# display_in4.net
KiCad netlist of a schematic drawn in EAGLE
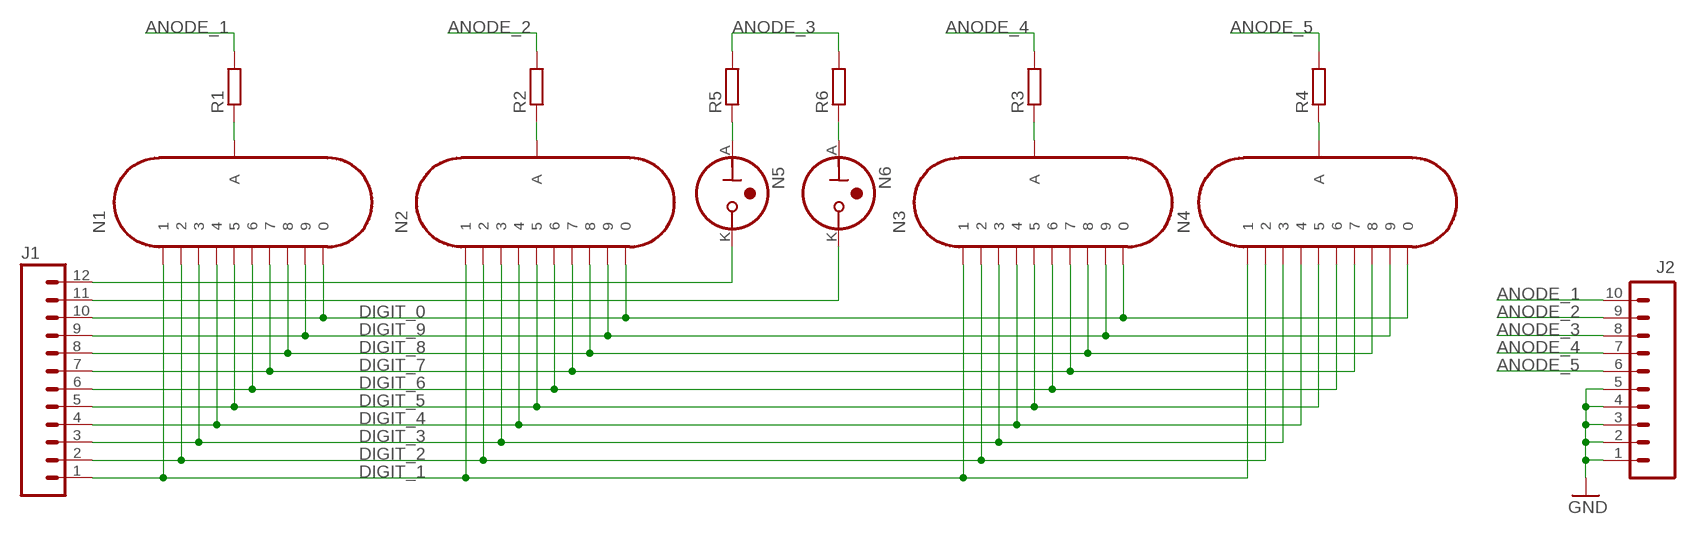
[diagram p0: schematic, sheet 1]

(export (version "E")
  (design (tool "Eeschema 10.0.6"))
  (components
    (comp (ref "J1")
      (value "M12LOCK")
      (footprint "eagle-import:1X12_LOCK")
      (libsource (lib "eagle-import") (part "M12LOCK"))
    )
    (comp (ref "J2")
      (value "M10LOCK")
      (footprint "eagle-import:1X10_LOCK")
      (libsource (lib "eagle-import") (part "M10LOCK"))
    )
    (comp (ref "N1")
      (value "IN-4")
      (footprint "eagle-import:IN-4")
      (libsource (lib "eagle-import") (part "IN-4"))
    )
    (comp (ref "N2")
      (value "IN-4")
      (footprint "eagle-import:IN-4")
      (libsource (lib "eagle-import") (part "IN-4"))
    )
    (comp (ref "N3")
      (value "IN-4")
      (footprint "eagle-import:IN-4")
      (libsource (lib "eagle-import") (part "IN-4"))
    )
    (comp (ref "N4")
      (value "IN-4")
      (footprint "eagle-import:IN-4")
      (libsource (lib "eagle-import") (part "IN-4"))
    )
    (comp (ref "N5")
      (value "IN-6")
      (footprint "eagle-import:IN-6")
      (libsource (lib "eagle-import") (part "IN-6"))
    )
    (comp (ref "N6")
      (value "IN-6")
      (footprint "eagle-import:IN-6")
      (libsource (lib "eagle-import") (part "IN-6"))
    )
    (comp (ref "R1")
      (value "R-EU_0204/7")
      (footprint "eagle-import:0204_7")
      (libsource (lib "eagle-import") (part "R-EU_0204/7"))
    )
    (comp (ref "R2")
      (value "R-EU_0204/7")
      (footprint "eagle-import:0204_7")
      (libsource (lib "eagle-import") (part "R-EU_0204/7"))
    )
    (comp (ref "R3")
      (value "R-EU_0204/7")
      (footprint "eagle-import:0204_7")
      (libsource (lib "eagle-import") (part "R-EU_0204/7"))
    )
    (comp (ref "R4")
      (value "R-EU_0204/7")
      (footprint "eagle-import:0204_7")
      (libsource (lib "eagle-import") (part "R-EU_0204/7"))
    )
    (comp (ref "R5")
      (value "R-EU_0204/7")
      (footprint "eagle-import:0204_7")
      (libsource (lib "eagle-import") (part "R-EU_0204/7"))
    )
    (comp (ref "R6")
      (value "R-EU_0204/7")
      (footprint "eagle-import:0204_7")
      (libsource (lib "eagle-import") (part "R-EU_0204/7"))
    )
  )
  (nets
    (net (code "1") (name "/ANODE_1") (class "Default")
      (node (ref "J2") (pin "10") (pinfunction "10_10") (pintype "passive"))
      (node (ref "R1") (pin "2") (pinfunction "2_2") (pintype "passive"))
    )
    (net (code "2") (name "/ANODE_2") (class "Default")
      (node (ref "J2") (pin "9") (pinfunction "9_9") (pintype "passive"))
      (node (ref "R2") (pin "2") (pinfunction "2_2") (pintype "passive"))
    )
    (net (code "3") (name "/ANODE_3") (class "Default")
      (node (ref "J2") (pin "8") (pinfunction "8_8") (pintype "passive"))
      (node (ref "R5") (pin "2") (pinfunction "2_2") (pintype "passive"))
      (node (ref "R6") (pin "2") (pinfunction "2_2") (pintype "passive"))
    )
    (net (code "4") (name "/ANODE_4") (class "Default")
      (node (ref "J2") (pin "7") (pinfunction "7_7") (pintype "passive"))
      (node (ref "R3") (pin "2") (pinfunction "2_2") (pintype "passive"))
    )
    (net (code "5") (name "/ANODE_5") (class "Default")
      (node (ref "J2") (pin "6") (pinfunction "6_6") (pintype "passive"))
      (node (ref "R4") (pin "2") (pinfunction "2_2") (pintype "passive"))
    )
    (net (code "6") (name "/DIGIT_0") (class "Default")
      (node (ref "J1") (pin "10") (pinfunction "10_10") (pintype "passive"))
      (node (ref "N1") (pin "8") (pinfunction "0_8") (pintype "bidirectional"))
      (node (ref "N2") (pin "8") (pinfunction "0_8") (pintype "bidirectional"))
      (node (ref "N3") (pin "8") (pinfunction "0_8") (pintype "bidirectional"))
      (node (ref "N4") (pin "8") (pinfunction "0_8") (pintype "bidirectional"))
    )
    (net (code "7") (name "/DIGIT_1") (class "Default")
      (node (ref "J1") (pin "1") (pinfunction "1_1") (pintype "passive"))
      (node (ref "N1") (pin "14") (pinfunction "1_14") (pintype "bidirectional"))
      (node (ref "N2") (pin "14") (pinfunction "1_14") (pintype "bidirectional"))
      (node (ref "N3") (pin "14") (pinfunction "1_14") (pintype "bidirectional"))
      (node (ref "N4") (pin "14") (pinfunction "1_14") (pintype "bidirectional"))
    )
    (net (code "8") (name "/DIGIT_2") (class "Default")
      (node (ref "J1") (pin "2") (pinfunction "2_2") (pintype "passive"))
      (node (ref "N1") (pin "9") (pinfunction "2_9") (pintype "bidirectional"))
      (node (ref "N2") (pin "9") (pinfunction "2_9") (pintype "bidirectional"))
      (node (ref "N3") (pin "9") (pinfunction "2_9") (pintype "bidirectional"))
      (node (ref "N4") (pin "9") (pinfunction "2_9") (pintype "bidirectional"))
    )
    (net (code "9") (name "/DIGIT_3") (class "Default")
      (node (ref "J1") (pin "3") (pinfunction "3_3") (pintype "passive"))
      (node (ref "N1") (pin "11") (pinfunction "3_11") (pintype "bidirectional"))
      (node (ref "N2") (pin "11") (pinfunction "3_11") (pintype "bidirectional"))
      (node (ref "N3") (pin "11") (pinfunction "3_11") (pintype "bidirectional"))
      (node (ref "N4") (pin "11") (pinfunction "3_11") (pintype "bidirectional"))
    )
    (net (code "10") (name "/DIGIT_4") (class "Default")
      (node (ref "J1") (pin "4") (pinfunction "4_4") (pintype "passive"))
      (node (ref "N1") (pin "1") (pinfunction "4_1") (pintype "bidirectional"))
      (node (ref "N2") (pin "1") (pinfunction "4_1") (pintype "bidirectional"))
      (node (ref "N3") (pin "1") (pinfunction "4_1") (pintype "bidirectional"))
      (node (ref "N4") (pin "1") (pinfunction "4_1") (pintype "bidirectional"))
    )
    (net (code "11") (name "/DIGIT_5") (class "Default")
      (node (ref "J1") (pin "5") (pinfunction "5_5") (pintype "passive"))
      (node (ref "N1") (pin "12") (pinfunction "5_12") (pintype "bidirectional"))
      (node (ref "N2") (pin "12") (pinfunction "5_12") (pintype "bidirectional"))
      (node (ref "N3") (pin "12") (pinfunction "5_12") (pintype "bidirectional"))
      (node (ref "N4") (pin "12") (pinfunction "5_12") (pintype "bidirectional"))
    )
    (net (code "12") (name "/DIGIT_6") (class "Default")
      (node (ref "J1") (pin "6") (pinfunction "6_6") (pintype "passive"))
      (node (ref "N1") (pin "2") (pinfunction "6_2") (pintype "bidirectional"))
      (node (ref "N2") (pin "2") (pinfunction "6_2") (pintype "bidirectional"))
      (node (ref "N3") (pin "2") (pinfunction "6_2") (pintype "bidirectional"))
      (node (ref "N4") (pin "2") (pinfunction "6_2") (pintype "bidirectional"))
    )
    (net (code "13") (name "/DIGIT_7") (class "Default")
      (node (ref "J1") (pin "7") (pinfunction "7_7") (pintype "passive"))
      (node (ref "N1") (pin "6") (pinfunction "7_6") (pintype "bidirectional"))
      (node (ref "N2") (pin "6") (pinfunction "7_6") (pintype "bidirectional"))
      (node (ref "N3") (pin "6") (pinfunction "7_6") (pintype "bidirectional"))
      (node (ref "N4") (pin "6") (pinfunction "7_6") (pintype "bidirectional"))
    )
    (net (code "14") (name "/DIGIT_8") (class "Default")
      (node (ref "J1") (pin "8") (pinfunction "8_8") (pintype "passive"))
      (node (ref "N1") (pin "3") (pinfunction "8_3") (pintype "bidirectional"))
      (node (ref "N2") (pin "3") (pinfunction "8_3") (pintype "bidirectional"))
      (node (ref "N3") (pin "3") (pinfunction "8_3") (pintype "bidirectional"))
      (node (ref "N4") (pin "3") (pinfunction "8_3") (pintype "bidirectional"))
    )
    (net (code "15") (name "/DIGIT_9") (class "Default")
      (node (ref "J1") (pin "9") (pinfunction "9_9") (pintype "passive"))
      (node (ref "N1") (pin "5") (pinfunction "9_5") (pintype "bidirectional"))
      (node (ref "N2") (pin "5") (pinfunction "9_5") (pintype "bidirectional"))
      (node (ref "N3") (pin "5") (pinfunction "9_5") (pintype "bidirectional"))
      (node (ref "N4") (pin "5") (pinfunction "9_5") (pintype "bidirectional"))
    )
    (net (code "16") (name "GND") (class "Default")
      (node (ref "J2") (pin "1") (pinfunction "1_1") (pintype "passive"))
      (node (ref "J2") (pin "2") (pinfunction "2_2") (pintype "passive"))
      (node (ref "J2") (pin "3") (pinfunction "3_3") (pintype "passive"))
      (node (ref "J2") (pin "4") (pinfunction "4_4") (pintype "passive"))
      (node (ref "J2") (pin "5") (pinfunction "5_5") (pintype "passive"))
    )
    (net (code "17") (name "Net-(J1-Pad11)") (class "Default")
      (node (ref "J1") (pin "11") (pinfunction "11_11") (pintype "passive"))
      (node (ref "N6") (pin "K") (pinfunction "K_K") (pintype "bidirectional"))
    )
    (net (code "18") (name "Net-(J1-Pad12)") (class "Default")
      (node (ref "J1") (pin "12") (pinfunction "12_12") (pintype "passive"))
      (node (ref "N5") (pin "K") (pinfunction "K_K") (pintype "bidirectional"))
    )
    (net (code "19") (name "Net-(N1-A)") (class "Default")
      (node (ref "N1") (pin "4") (pinfunction "A_4") (pintype "bidirectional"))
      (node (ref "R1") (pin "1") (pinfunction "1_1") (pintype "passive"))
    )
    (net (code "20") (name "Net-(N2-A)") (class "Default")
      (node (ref "N2") (pin "4") (pinfunction "A_4") (pintype "bidirectional"))
      (node (ref "R2") (pin "1") (pinfunction "1_1") (pintype "passive"))
    )
    (net (code "21") (name "Net-(N3-A)") (class "Default")
      (node (ref "N3") (pin "4") (pinfunction "A_4") (pintype "bidirectional"))
      (node (ref "R3") (pin "1") (pinfunction "1_1") (pintype "passive"))
    )
    (net (code "22") (name "Net-(N4-A)") (class "Default")
      (node (ref "N4") (pin "4") (pinfunction "A_4") (pintype "bidirectional"))
      (node (ref "R4") (pin "1") (pinfunction "1_1") (pintype "passive"))
    )
    (net (code "23") (name "Net-(N5-PadA)") (class "Default")
      (node (ref "N5") (pin "A") (pinfunction "A_A") (pintype "bidirectional"))
      (node (ref "R5") (pin "1") (pinfunction "1_1") (pintype "passive"))
    )
    (net (code "24") (name "Net-(N6-PadA)") (class "Default")
      (node (ref "N6") (pin "A") (pinfunction "A_A") (pintype "bidirectional"))
      (node (ref "R6") (pin "1") (pinfunction "1_1") (pintype "passive"))
    )
  )
)
